# main.net
KiCad netlist of a schematic drawn in EAGLE
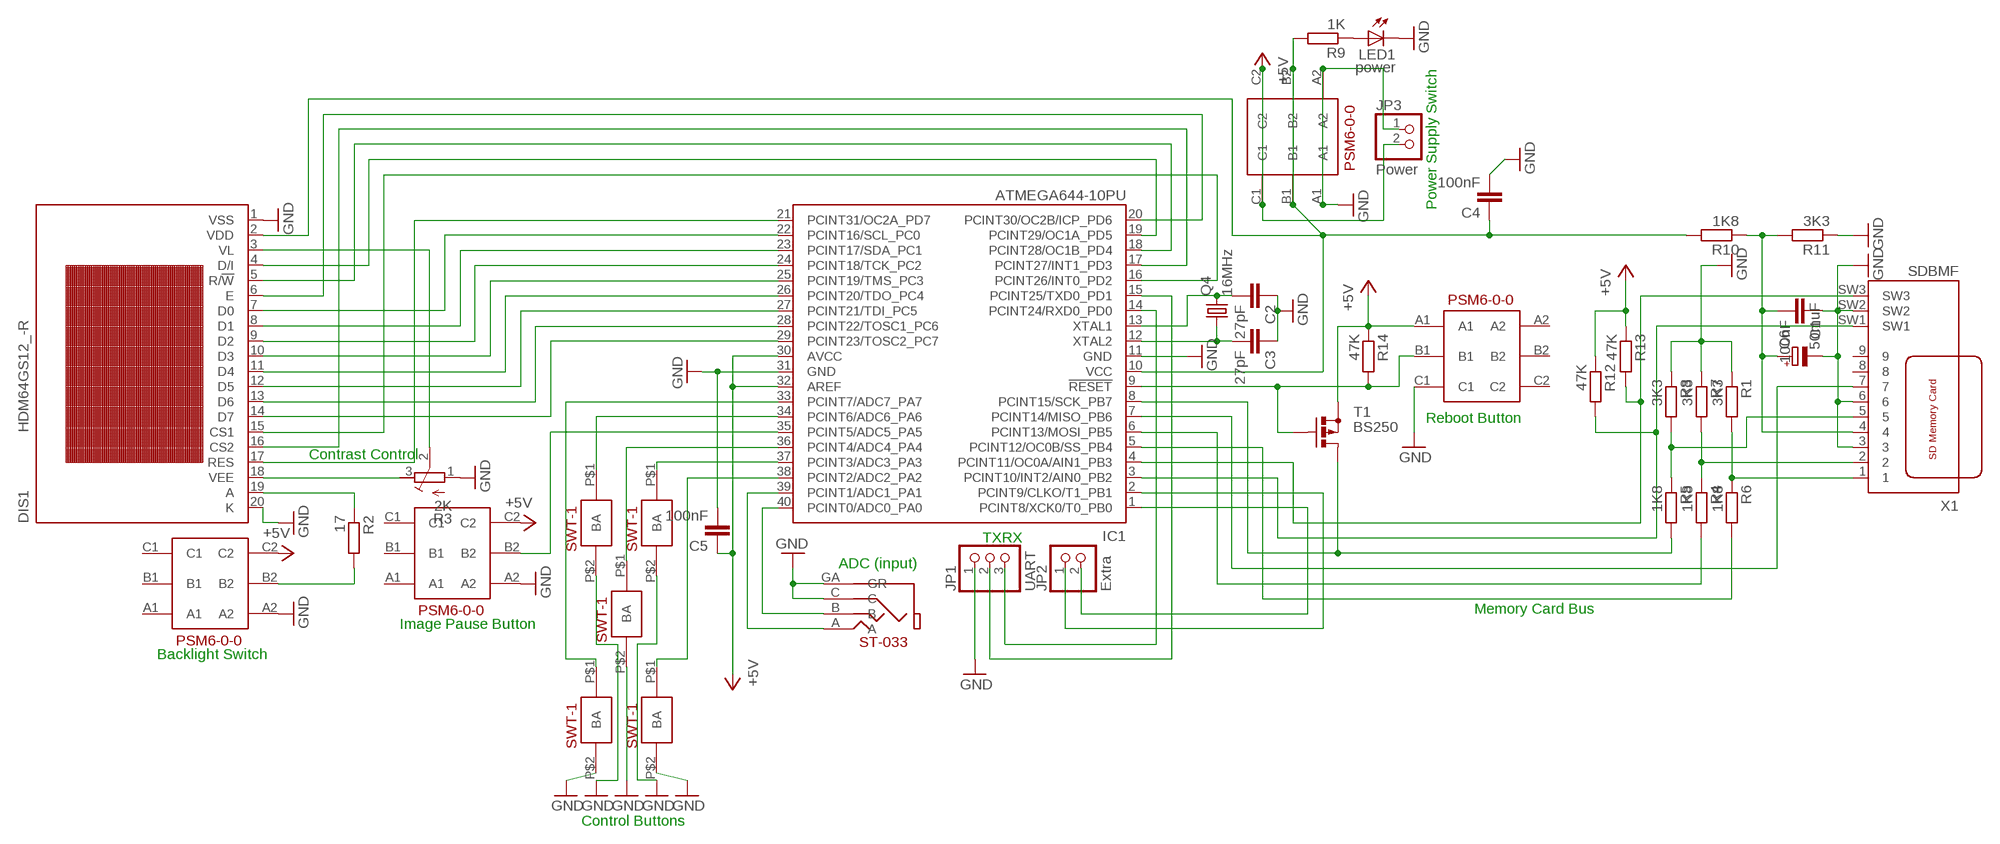
[diagram p0: schematic, sheet 1]

(export (version "E")
  (design (tool "Eeschema 10.0.6"))
  (components
    (comp (ref "C1")
      (value "100nF")
      (footprint "eagle-import:C050-075X075")
      (libsource (lib "eagle-import") (part "C-EU050-075X075"))
    )
    (comp (ref "C2")
      (value "27pF")
      (footprint "eagle-import:C050-075X075")
      (libsource (lib "eagle-import") (part "C-EU050-075X075"))
    )
    (comp (ref "C3")
      (value "27pF")
      (footprint "eagle-import:C050-075X075")
      (libsource (lib "eagle-import") (part "C-EU050-075X075"))
    )
    (comp (ref "C4")
      (value "100nF")
      (footprint "eagle-import:C050-075X075")
      (libsource (lib "eagle-import") (part "C-EU050-075X075"))
    )
    (comp (ref "C5")
      (value "100nF")
      (footprint "eagle-import:C050-075X075")
      (libsource (lib "eagle-import") (part "C-EU050-075X075"))
    )
    (comp (ref "C6")
      (value "50muF")
      (footprint "eagle-import:E5-13")
      (libsource (lib "eagle-import") (part "CPOL-EUE5-13"))
    )
    (comp (ref "DIS1")
      (value "HDM64GS12_-R")
      (footprint "eagle-import:HDM64GS12_-R")
      (libsource (lib "eagle-import") (part "HDM64GS12_-R"))
    )
    (comp (ref "IC1")
      (value "ATMEGA644-10PU")
      (footprint "eagle-import:DIL40")
      (fields (field (name "MPN") "ATMEGA644V-10PU"))
      (libsource (lib "eagle-import") (part "ATMEGA644-PU10"))
    )
    (comp (ref "JP1")
      (value "UART")
      (footprint "eagle-import:1X03")
      (libsource (lib "eagle-import") (part "PINHD-1X3"))
    )
    (comp (ref "JP2")
      (value "Extra")
      (footprint "eagle-import:1X02")
      (libsource (lib "eagle-import") (part "PINHD-1X2"))
    )
    (comp (ref "JP3")
      (value "Power")
      (footprint "eagle-import:1X02")
      (libsource (lib "eagle-import") (part "PINHD-1X2"))
    )
    (comp (ref "LED1")
      (value "power")
      (footprint "eagle-import:LED3MM")
      (libsource (lib "eagle-import") (part "LED3MM"))
    )
    (comp (ref "Q4")
      (value "16MHz")
      (footprint "eagle-import:HC49U-V")
      (libsource (lib "eagle-import") (part "CRYSTALHC49U-V"))
    )
    (comp (ref "R1")
      (value "3K3")
      (footprint "eagle-import:0204_7")
      (libsource (lib "eagle-import") (part "R-EU_0204/7"))
    )
    (comp (ref "R2")
      (value "17")
      (footprint "eagle-import:P0817_22")
      (libsource (lib "eagle-import") (part "R-EU_0817/22"))
    )
    (comp (ref "R3")
      (value "2K")
      (footprint "eagle-import:RTRIM4G_J")
      (libsource (lib "eagle-import") (part "R-TRIMM4G/J"))
    )
    (comp (ref "R4")
      (value "1K8")
      (footprint "eagle-import:0204_7")
      (libsource (lib "eagle-import") (part "R-EU_0204/7"))
    )
    (comp (ref "R5")
      (value "1K8")
      (footprint "eagle-import:0204_7")
      (libsource (lib "eagle-import") (part "R-EU_0204/7"))
    )
    (comp (ref "R6")
      (value "1K8")
      (footprint "eagle-import:0204_7")
      (libsource (lib "eagle-import") (part "R-EU_0204/7"))
    )
    (comp (ref "R7")
      (value "3K3")
      (footprint "eagle-import:0204_7")
      (libsource (lib "eagle-import") (part "R-EU_0204/7"))
    )
    (comp (ref "R8")
      (value "3K3")
      (footprint "eagle-import:0204_7")
      (libsource (lib "eagle-import") (part "R-EU_0204/7"))
    )
    (comp (ref "R9")
      (value "1K")
      (footprint "eagle-import:0204_7")
      (libsource (lib "eagle-import") (part "R-EU_0204/7"))
    )
    (comp (ref "R10")
      (value "1K8")
      (footprint "eagle-import:0204_7")
      (libsource (lib "eagle-import") (part "R-EU_0204/7"))
    )
    (comp (ref "R11")
      (value "3K3")
      (footprint "eagle-import:0204_7")
      (libsource (lib "eagle-import") (part "R-EU_0204/7"))
    )
    (comp (ref "R12")
      (value "47K")
      (footprint "eagle-import:0204_7")
      (libsource (lib "eagle-import") (part "R-EU_0204/7"))
    )
    (comp (ref "R13")
      (value "47K")
      (footprint "eagle-import:0204_7")
      (libsource (lib "eagle-import") (part "R-EU_0204/7"))
    )
    (comp (ref "R14")
      (value "47K")
      (footprint "eagle-import:0204_7")
      (libsource (lib "eagle-import") (part "R-EU_0204/7"))
    )
    (comp (ref "T1")
      (value "BS250")
      (footprint "eagle-import:SOT54E")
      (libsource (lib "eagle-import") (part "BS250"))
    )
    (comp (ref "U$1_TOP")
      (value "TOP")
      (footprint "eagle-import:SWT-1")
      (libsource (lib "eagle-import") (part "SWT-1"))
    )
    (comp (ref "U$2_RIGHT")
      (value "RIGHT")
      (footprint "eagle-import:SWT-1")
      (libsource (lib "eagle-import") (part "SWT-1"))
    )
    (comp (ref "U$3_LEFT")
      (value "LEFT")
      (footprint "eagle-import:SWT-1")
      (libsource (lib "eagle-import") (part "SWT-1"))
    )
    (comp (ref "U$4_BOTTOM")
      (value "BOTTOM")
      (footprint "eagle-import:SWT-1")
      (libsource (lib "eagle-import") (part "SWT-1"))
    )
    (comp (ref "U$5_CENTER")
      (value "CENTER")
      (footprint "eagle-import:SWT-1")
      (libsource (lib "eagle-import") (part "SWT-1"))
    )
    (comp (ref "U$6_BACKLIGHT")
      (value "pause")
      (footprint "eagle-import:PSM6-0-0")
      (libsource (lib "eagle-import") (part "PSM6-0-0"))
    )
    (comp (ref "U$6_PAUSE")
      (value "pause")
      (footprint "eagle-import:PSM6-0-0")
      (libsource (lib "eagle-import") (part "PSM6-0-0"))
    )
    (comp (ref "U$7_POWER")
      (value "power")
      (footprint "eagle-import:PSM6-0-0")
      (libsource (lib "eagle-import") (part "PSM6-0-0"))
    )
    (comp (ref "U$8_REBOOT")
      (value "reboot")
      (footprint "eagle-import:PSM6-0-0")
      (libsource (lib "eagle-import") (part "PSM6-0-0"))
    )
    (comp (ref "U$11")
      (value "ST-033")
      (footprint "eagle-import:ST-033")
      (libsource (lib "eagle-import") (part "ST-033"))
    )
    (comp (ref "X1")
      (value "SDBMF")
      (footprint "eagle-import:SDBMF-009XXBXX2")
      (libsource (lib "eagle-import") (part "SDBMF"))
    )
  )
  (nets
    (net (code "1") (name "+5V") (class "Default")
      (node (ref "C5") (pin "1") (pinfunction "1_1") (pintype "passive"))
      (node (ref "IC1") (pin "30") (pinfunction "AVCC_30") (pintype "power_in"))
      (node (ref "IC1") (pin "32") (pinfunction "AREF_32") (pintype "passive"))
      (node (ref "JP3") (pin "2") (pinfunction "2_2") (pintype "passive"))
      (node (ref "R12") (pin "1") (pinfunction "1_1") (pintype "passive"))
      (node (ref "R13") (pin "1") (pinfunction "1_1") (pintype "passive"))
      (node (ref "R14") (pin "1") (pinfunction "1_1") (pintype "passive"))
      (node (ref "T1") (pin "S") (pinfunction "S_S") (pintype "passive"))
      (node (ref "U$6_BACKLIGHT") (pin "C2") (pinfunction "C2_C2") (pintype "bidirectional"))
      (node (ref "U$6_PAUSE") (pin "C2") (pinfunction "C2_C2") (pintype "bidirectional"))
      (node (ref "U$7_POWER") (pin "C1") (pinfunction "C1_C1") (pintype "bidirectional"))
      (node (ref "U$7_POWER") (pin "C2") (pinfunction "C2_C2") (pintype "bidirectional"))
      (node (ref "U$8_REBOOT") (pin "A1") (pinfunction "A1_A1") (pintype "bidirectional"))
    )
    (net (code "2") (name "GND") (class "Default")
      (node (ref "C1") (pin "1") (pinfunction "1_1") (pintype "passive"))
      (node (ref "C2") (pin "1") (pinfunction "1_1") (pintype "passive"))
      (node (ref "C3") (pin "1") (pinfunction "1_1") (pintype "passive"))
      (node (ref "C4") (pin "2") (pinfunction "2_2") (pintype "passive"))
      (node (ref "C5") (pin "2") (pinfunction "2_2") (pintype "passive"))
      (node (ref "C6") (pin "-") (pinfunction "-_-") (pintype "passive"))
      (node (ref "DIS1") (pin "1") (pinfunction "VSS_1") (pintype "power_in"))
      (node (ref "DIS1") (pin "20") (pinfunction "K_20") (pintype "passive"))
      (node (ref "IC1") (pin "11") (pinfunction "GND_11") (pintype "power_in"))
      (node (ref "IC1") (pin "31") (pinfunction "GND_31") (pintype "power_in"))
      (node (ref "JP1") (pin "1") (pinfunction "1_1") (pintype "passive"))
      (node (ref "JP3") (pin "1") (pinfunction "1_1") (pintype "passive"))
      (node (ref "LED1") (pin "K") (pinfunction "C_K") (pintype "passive"))
      (node (ref "R1") (pin "1") (pinfunction "1_1") (pintype "passive"))
      (node (ref "R11") (pin "1") (pinfunction "1_1") (pintype "passive"))
      (node (ref "R3") (pin "1") (pinfunction "E_1") (pintype "passive"))
      (node (ref "R7") (pin "1") (pinfunction "1_1") (pintype "passive"))
      (node (ref "R8") (pin "1") (pinfunction "1_1") (pintype "passive"))
      (node (ref "U$11") (pin "C") (pinfunction "C_C") (pintype "bidirectional"))
      (node (ref "U$11") (pin "GA") (pinfunction "GR_GA") (pintype "bidirectional"))
      (node (ref "U$1_TOP") (pin "P$2") (pinfunction "B_P$2") (pintype "bidirectional"))
      (node (ref "U$2_RIGHT") (pin "P$2") (pinfunction "B_P$2") (pintype "bidirectional"))
      (node (ref "U$3_LEFT") (pin "P$2") (pinfunction "B_P$2") (pintype "bidirectional"))
      (node (ref "U$4_BOTTOM") (pin "P$2") (pinfunction "B_P$2") (pintype "bidirectional"))
      (node (ref "U$5_CENTER") (pin "P$2") (pinfunction "B_P$2") (pintype "bidirectional"))
      (node (ref "U$6_BACKLIGHT") (pin "A2") (pinfunction "A2_A2") (pintype "bidirectional"))
      (node (ref "U$6_PAUSE") (pin "A2") (pinfunction "A2_A2") (pintype "bidirectional"))
      (node (ref "U$7_POWER") (pin "A1") (pinfunction "A1_A1") (pintype "bidirectional"))
      (node (ref "U$7_POWER") (pin "A2") (pinfunction "A2_A2") (pintype "bidirectional"))
      (node (ref "U$8_REBOOT") (pin "C1") (pinfunction "C1_C1") (pintype "bidirectional"))
      (node (ref "X1") (pin "3") (pinfunction "3_3") (pintype "passive"))
      (node (ref "X1") (pin "6") (pinfunction "6_6") (pintype "passive"))
      (node (ref "X1") (pin "SW2") (pinfunction "SW2_SW2") (pintype "passive"))
    )
    (net (code "3") (name "Net-(C1-Pad2)") (class "Default")
      (node (ref "C1") (pin "2") (pinfunction "2_2") (pintype "passive"))
      (node (ref "C6") (pin "+") (pinfunction "+_+") (pintype "passive"))
      (node (ref "R10") (pin "1") (pinfunction "1_1") (pintype "passive"))
      (node (ref "R11") (pin "2") (pinfunction "2_2") (pintype "passive"))
      (node (ref "X1") (pin "4") (pinfunction "4_4") (pintype "passive"))
    )
    (net (code "4") (name "Net-(DIS1-A)") (class "Default")
      (node (ref "DIS1") (pin "19") (pinfunction "A_19") (pintype "passive"))
      (node (ref "R2") (pin "1") (pinfunction "1_1") (pintype "passive"))
    )
    (net (code "5") (name "Net-(DIS1-CS1)") (class "Default")
      (node (ref "DIS1") (pin "15") (pinfunction "CS1_15") (pintype "input"))
      (node (ref "IC1") (pin "16") (pinfunction "PCINT26/INT0_PD2_16") (pintype "bidirectional"))
    )
    (net (code "6") (name "Net-(DIS1-CS2)") (class "Default")
      (node (ref "DIS1") (pin "16") (pinfunction "CS2_16") (pintype "input"))
      (node (ref "IC1") (pin "17") (pinfunction "PCINT27/INT1_PD3_17") (pintype "bidirectional"))
    )
    (net (code "7") (name "Net-(DIS1-D0)") (class "Default")
      (node (ref "DIS1") (pin "7") (pinfunction "D0_7") (pintype "bidirectional"))
      (node (ref "IC1") (pin "22") (pinfunction "PCINT16/SCL_PC0_22") (pintype "bidirectional"))
    )
    (net (code "8") (name "Net-(DIS1-D1)") (class "Default")
      (node (ref "DIS1") (pin "8") (pinfunction "D1_8") (pintype "bidirectional"))
      (node (ref "IC1") (pin "23") (pinfunction "PCINT17/SDA_PC1_23") (pintype "bidirectional"))
    )
    (net (code "9") (name "Net-(DIS1-D2)") (class "Default")
      (node (ref "DIS1") (pin "9") (pinfunction "D2_9") (pintype "bidirectional"))
      (node (ref "IC1") (pin "24") (pinfunction "PCINT18/TCK_PC2_24") (pintype "bidirectional"))
    )
    (net (code "10") (name "Net-(DIS1-D3)") (class "Default")
      (node (ref "DIS1") (pin "10") (pinfunction "D3_10") (pintype "bidirectional"))
      (node (ref "IC1") (pin "25") (pinfunction "PCINT19/TMS_PC3_25") (pintype "bidirectional"))
    )
    (net (code "11") (name "Net-(DIS1-D4)") (class "Default")
      (node (ref "DIS1") (pin "11") (pinfunction "D4_11") (pintype "bidirectional"))
      (node (ref "IC1") (pin "26") (pinfunction "PCINT20/TDO_PC4_26") (pintype "bidirectional"))
    )
    (net (code "12") (name "Net-(DIS1-D5)") (class "Default")
      (node (ref "DIS1") (pin "12") (pinfunction "D5_12") (pintype "bidirectional"))
      (node (ref "IC1") (pin "27") (pinfunction "PCINT21/TDI_PC5_27") (pintype "bidirectional"))
    )
    (net (code "13") (name "Net-(DIS1-D6)") (class "Default")
      (node (ref "DIS1") (pin "13") (pinfunction "D6_13") (pintype "bidirectional"))
      (node (ref "IC1") (pin "28") (pinfunction "PCINT22/TOSC1_PC6_28") (pintype "bidirectional"))
    )
    (net (code "14") (name "Net-(DIS1-D7)") (class "Default")
      (node (ref "DIS1") (pin "14") (pinfunction "D7_14") (pintype "bidirectional"))
      (node (ref "IC1") (pin "29") (pinfunction "PCINT23/TOSC2_PC7_29") (pintype "bidirectional"))
    )
    (net (code "15") (name "Net-(DIS1-D{slash}I)") (class "Default")
      (node (ref "DIS1") (pin "4") (pinfunction "D/I_4") (pintype "input"))
      (node (ref "IC1") (pin "19") (pinfunction "PCINT29/OC1A_PD5_19") (pintype "bidirectional"))
    )
    (net (code "16") (name "Net-(DIS1-E)") (class "Default")
      (node (ref "DIS1") (pin "6") (pinfunction "E_6") (pintype "input"))
      (node (ref "IC1") (pin "20") (pinfunction "PCINT30/OC2B/ICP_PD6_20") (pintype "bidirectional"))
    )
    (net (code "17") (name "Net-(DIS1-RES)") (class "Default")
      (node (ref "DIS1") (pin "17") (pinfunction "RES_17") (pintype "input"))
      (node (ref "IC1") (pin "21") (pinfunction "PCINT31/OC2A_PD7_21") (pintype "bidirectional"))
    )
    (net (code "18") (name "Net-(DIS1-R{slash}~{W})") (class "Default")
      (node (ref "DIS1") (pin "5") (pinfunction "R/~{W}_5") (pintype "input"))
      (node (ref "IC1") (pin "18") (pinfunction "PCINT28/OC1B_PD4_18") (pintype "bidirectional"))
    )
    (net (code "19") (name "Net-(DIS1-VDD)") (class "Default")
      (node (ref "C4") (pin "1") (pinfunction "1_1") (pintype "passive"))
      (node (ref "DIS1") (pin "2") (pinfunction "VDD_2") (pintype "power_in"))
      (node (ref "IC1") (pin "10") (pinfunction "VCC_10") (pintype "power_in"))
      (node (ref "R10") (pin "2") (pinfunction "2_2") (pintype "passive"))
      (node (ref "R9") (pin "2") (pinfunction "2_2") (pintype "passive"))
      (node (ref "U$7_POWER") (pin "B1") (pinfunction "B1_B1") (pintype "bidirectional"))
      (node (ref "U$7_POWER") (pin "B2") (pinfunction "B2_B2") (pintype "bidirectional"))
    )
    (net (code "20") (name "Net-(DIS1-VEE)") (class "Default")
      (node (ref "DIS1") (pin "18") (pinfunction "VEE_18") (pintype "output"))
      (node (ref "R3") (pin "3") (pinfunction "A_3") (pintype "passive"))
    )
    (net (code "21") (name "Net-(DIS1-VL)") (class "Default")
      (node (ref "DIS1") (pin "3") (pinfunction "VL_3") (pintype "passive"))
      (node (ref "R3") (pin "2") (pinfunction "S_2") (pintype "passive"))
    )
    (net (code "22") (name "Net-(IC1-PCINT0{slash}ADC0_PA0)") (class "Default")
      (node (ref "IC1") (pin "40") (pinfunction "PCINT0/ADC0_PA0_40") (pintype "bidirectional"))
      (node (ref "U$11") (pin "B") (pinfunction "B_B") (pintype "bidirectional"))
    )
    (net (code "23") (name "Net-(IC1-PCINT1{slash}ADC1_PA1)") (class "Default")
      (node (ref "IC1") (pin "39") (pinfunction "PCINT1/ADC1_PA1_39") (pintype "bidirectional"))
      (node (ref "U$11") (pin "A") (pinfunction "A_A") (pintype "bidirectional"))
    )
    (net (code "24") (name "Net-(IC1-PCINT2{slash}ADC2_PA2)") (class "Default")
      (node (ref "IC1") (pin "38") (pinfunction "PCINT2/ADC2_PA2_38") (pintype "bidirectional"))
      (node (ref "U$5_CENTER") (pin "P$1") (pinfunction "A_P$1") (pintype "bidirectional"))
    )
    (net (code "25") (name "Net-(IC1-PCINT3{slash}ADC3_PA3)") (class "Default")
      (node (ref "IC1") (pin "37") (pinfunction "PCINT3/ADC3_PA3_37") (pintype "bidirectional"))
      (node (ref "U$2_RIGHT") (pin "P$1") (pinfunction "A_P$1") (pintype "bidirectional"))
    )
    (net (code "26") (name "Net-(IC1-PCINT4{slash}ADC4_PA4)") (class "Default")
      (node (ref "IC1") (pin "36") (pinfunction "PCINT4/ADC4_PA4_36") (pintype "bidirectional"))
      (node (ref "U$3_LEFT") (pin "P$1") (pinfunction "A_P$1") (pintype "bidirectional"))
    )
    (net (code "27") (name "Net-(IC1-PCINT5{slash}ADC5_PA5)") (class "Default")
      (node (ref "IC1") (pin "35") (pinfunction "PCINT5/ADC5_PA5_35") (pintype "bidirectional"))
      (node (ref "U$6_PAUSE") (pin "B2") (pinfunction "B2_B2") (pintype "bidirectional"))
    )
    (net (code "28") (name "Net-(IC1-PCINT6{slash}ADC6_PA6)") (class "Default")
      (node (ref "IC1") (pin "34") (pinfunction "PCINT6/ADC6_PA6_34") (pintype "bidirectional"))
      (node (ref "U$1_TOP") (pin "P$1") (pinfunction "A_P$1") (pintype "bidirectional"))
    )
    (net (code "29") (name "Net-(IC1-PCINT7{slash}ADC7_PA7)") (class "Default")
      (node (ref "IC1") (pin "33") (pinfunction "PCINT7/ADC7_PA7_33") (pintype "bidirectional"))
      (node (ref "U$4_BOTTOM") (pin "P$1") (pinfunction "A_P$1") (pintype "bidirectional"))
    )
    (net (code "30") (name "Net-(IC1-PCINT8{slash}XCK0{slash}T0_PB0)") (class "Default")
      (node (ref "IC1") (pin "1") (pinfunction "PCINT8/XCK0/T0_PB0_1") (pintype "bidirectional"))
      (node (ref "JP2") (pin "2") (pinfunction "2_2") (pintype "passive"))
    )
    (net (code "31") (name "Net-(IC1-PCINT9{slash}CLKO{slash}T1_PB1)") (class "Default")
      (node (ref "IC1") (pin "2") (pinfunction "PCINT9/CLKO/T1_PB1_2") (pintype "bidirectional"))
      (node (ref "JP2") (pin "1") (pinfunction "1_1") (pintype "passive"))
    )
    (net (code "32") (name "Net-(IC1-PCINT10{slash}INT2{slash}AIN0_PB2)") (class "Default")
      (node (ref "IC1") (pin "3") (pinfunction "PCINT10/INT2/AIN0_PB2_3") (pintype "bidirectional"))
      (node (ref "R12") (pin "2") (pinfunction "2_2") (pintype "passive"))
      (node (ref "X1") (pin "SW1") (pinfunction "SW1_SW1") (pintype "passive"))
    )
    (net (code "33") (name "Net-(IC1-PCINT11{slash}OC0A{slash}AIN1_PB3)") (class "Default")
      (node (ref "IC1") (pin "4") (pinfunction "PCINT11/OC0A/AIN1_PB3_4") (pintype "bidirectional"))
      (node (ref "R13") (pin "2") (pinfunction "2_2") (pintype "passive"))
      (node (ref "X1") (pin "SW3") (pinfunction "SW3_SW3") (pintype "passive"))
    )
    (net (code "34") (name "Net-(IC1-PCINT12{slash}OC0B{slash}SS_PB4)") (class "Default")
      (node (ref "IC1") (pin "5") (pinfunction "PCINT12/OC0B/SS_PB4_5") (pintype "bidirectional"))
      (node (ref "R6") (pin "2") (pinfunction "2_2") (pintype "passive"))
    )
    (net (code "35") (name "Net-(IC1-PCINT13{slash}MOSI_PB5)") (class "Default")
      (node (ref "IC1") (pin "6") (pinfunction "PCINT13/MOSI_PB5_6") (pintype "bidirectional"))
      (node (ref "R4") (pin "2") (pinfunction "2_2") (pintype "passive"))
    )
    (net (code "36") (name "Net-(IC1-PCINT14{slash}MISO_PB6)") (class "Default")
      (node (ref "IC1") (pin "7") (pinfunction "PCINT14/MISO_PB6_7") (pintype "bidirectional"))
      (node (ref "X1") (pin "7") (pinfunction "7_7") (pintype "passive"))
    )
    (net (code "37") (name "Net-(IC1-PCINT15{slash}SCK_PB7)") (class "Default")
      (node (ref "IC1") (pin "8") (pinfunction "PCINT15/SCK_PB7_8") (pintype "bidirectional"))
      (node (ref "R5") (pin "2") (pinfunction "2_2") (pintype "passive"))
      (node (ref "T1") (pin "D") (pinfunction "D_D") (pintype "passive"))
    )
    (net (code "38") (name "Net-(IC1-PCINT24{slash}RXD0_PD0)") (class "Default")
      (node (ref "IC1") (pin "14") (pinfunction "PCINT24/RXD0_PD0_14") (pintype "bidirectional"))
      (node (ref "JP1") (pin "3") (pinfunction "3_3") (pintype "passive"))
    )
    (net (code "39") (name "Net-(IC1-PCINT25{slash}TXD0_PD1)") (class "Default")
      (node (ref "IC1") (pin "15") (pinfunction "PCINT25/TXD0_PD1_15") (pintype "bidirectional"))
      (node (ref "JP1") (pin "2") (pinfunction "2_2") (pintype "passive"))
    )
    (net (code "40") (name "Net-(IC1-XTAL1)") (class "Default")
      (node (ref "C2") (pin "2") (pinfunction "2_2") (pintype "passive"))
      (node (ref "IC1") (pin "13") (pinfunction "XTAL1_13") (pintype "input"))
      (node (ref "Q4") (pin "2") (pinfunction "2_2") (pintype "passive"))
    )
    (net (code "41") (name "Net-(IC1-XTAL2)") (class "Default")
      (node (ref "C3") (pin "2") (pinfunction "2_2") (pintype "passive"))
      (node (ref "IC1") (pin "12") (pinfunction "XTAL2_12") (pintype "output"))
      (node (ref "Q4") (pin "1") (pinfunction "1_1") (pintype "passive"))
    )
    (net (code "42") (name "Net-(IC1-~{RESET})") (class "Default")
      (node (ref "IC1") (pin "9") (pinfunction "~{RESET}_9") (pintype "input"))
      (node (ref "R14") (pin "2") (pinfunction "2_2") (pintype "passive"))
      (node (ref "T1") (pin "G") (pinfunction "G_G") (pintype "passive"))
      (node (ref "U$8_REBOOT") (pin "B1") (pinfunction "B1_B1") (pintype "bidirectional"))
    )
    (net (code "43") (name "Net-(LED1-PadA)") (class "Default")
      (node (ref "LED1") (pin "A") (pinfunction "A_A") (pintype "passive"))
      (node (ref "R9") (pin "1") (pinfunction "1_1") (pintype "passive"))
    )
    (net (code "44") (name "Net-(R1-Pad2)") (class "Default")
      (node (ref "R1") (pin "2") (pinfunction "2_2") (pintype "passive"))
      (node (ref "R6") (pin "1") (pinfunction "1_1") (pintype "passive"))
      (node (ref "X1") (pin "1") (pinfunction "1_1") (pintype "passive"))
    )
    (net (code "45") (name "Net-(R2-Pad2)") (class "Default")
      (node (ref "R2") (pin "2") (pinfunction "2_2") (pintype "passive"))
      (node (ref "U$6_BACKLIGHT") (pin "B2") (pinfunction "B2_B2") (pintype "bidirectional"))
    )
    (net (code "46") (name "Net-(R4-Pad1)") (class "Default")
      (node (ref "R4") (pin "1") (pinfunction "1_1") (pintype "passive"))
      (node (ref "R7") (pin "2") (pinfunction "2_2") (pintype "passive"))
      (node (ref "X1") (pin "2") (pinfunction "2_2") (pintype "passive"))
    )
    (net (code "47") (name "Net-(R5-Pad1)") (class "Default")
      (node (ref "R5") (pin "1") (pinfunction "1_1") (pintype "passive"))
      (node (ref "R8") (pin "2") (pinfunction "2_2") (pintype "passive"))
      (node (ref "X1") (pin "5") (pinfunction "5_5") (pintype "passive"))
    )
    (net (code "48") (name "unconnected-(U$6_BACKLIGHT-PadA1)") (class "Default")
      (node (ref "U$6_BACKLIGHT") (pin "A1") (pinfunction "A1_A1") (pintype "bidirectional"))
    )
    (net (code "49") (name "unconnected-(U$6_BACKLIGHT-PadB1)") (class "Default")
      (node (ref "U$6_BACKLIGHT") (pin "B1") (pinfunction "B1_B1") (pintype "bidirectional"))
    )
    (net (code "50") (name "unconnected-(U$6_BACKLIGHT-PadC1)") (class "Default")
      (node (ref "U$6_BACKLIGHT") (pin "C1") (pinfunction "C1_C1") (pintype "bidirectional"))
    )
    (net (code "51") (name "unconnected-(U$6_PAUSE-PadA1)") (class "Default")
      (node (ref "U$6_PAUSE") (pin "A1") (pinfunction "A1_A1") (pintype "bidirectional"))
    )
    (net (code "52") (name "unconnected-(U$6_PAUSE-PadB1)") (class "Default")
      (node (ref "U$6_PAUSE") (pin "B1") (pinfunction "B1_B1") (pintype "bidirectional"))
    )
    (net (code "53") (name "unconnected-(U$6_PAUSE-PadC1)") (class "Default")
      (node (ref "U$6_PAUSE") (pin "C1") (pinfunction "C1_C1") (pintype "bidirectional"))
    )
    (net (code "54") (name "unconnected-(U$8_REBOOT-PadA2)") (class "Default")
      (node (ref "U$8_REBOOT") (pin "A2") (pinfunction "A2_A2") (pintype "bidirectional"))
    )
    (net (code "55") (name "unconnected-(U$8_REBOOT-PadB2)") (class "Default")
      (node (ref "U$8_REBOOT") (pin "B2") (pinfunction "B2_B2") (pintype "bidirectional"))
    )
    (net (code "56") (name "unconnected-(U$8_REBOOT-PadC2)") (class "Default")
      (node (ref "U$8_REBOOT") (pin "C2") (pinfunction "C2_C2") (pintype "bidirectional"))
    )
    (net (code "57") (name "unconnected-(X1-Pad8)") (class "Default")
      (node (ref "X1") (pin "8") (pinfunction "8_8") (pintype "passive"))
    )
    (net (code "58") (name "unconnected-(X1-Pad9)") (class "Default")
      (node (ref "X1") (pin "9") (pinfunction "9_9") (pintype "passive"))
    )
  )
)
